# GSM_GPS.net
KiCad netlist of a schematic drawn in Altium Designer
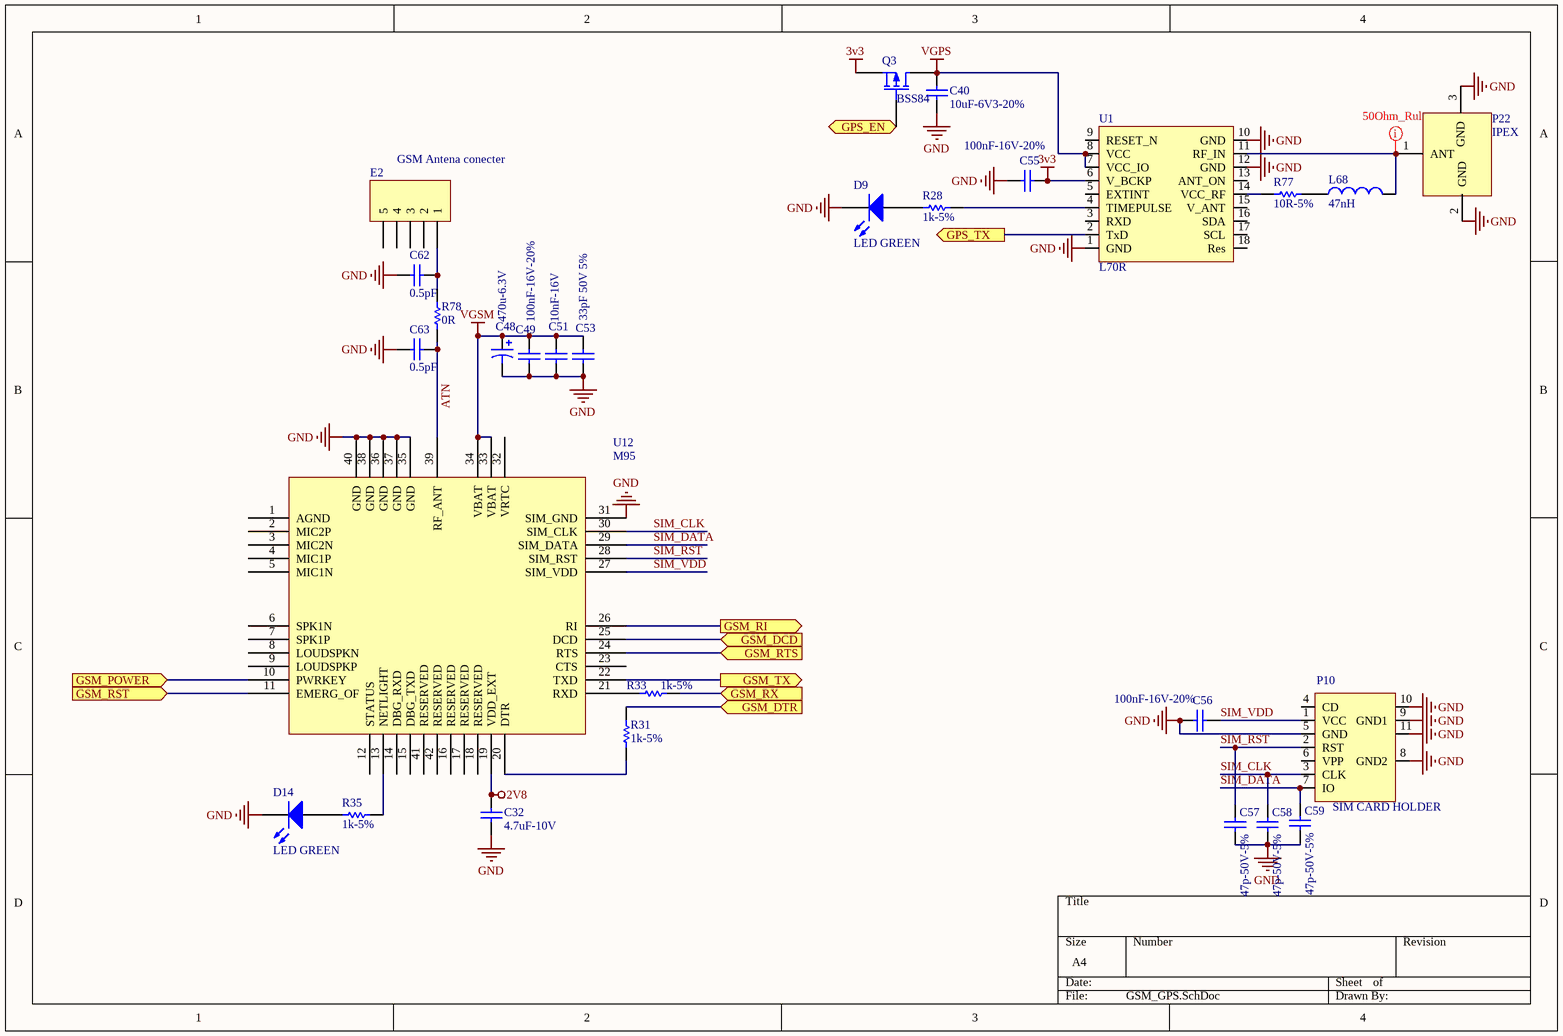
[diagram p0: GSM_GPS.SchDoc]

(export (version "E")
  (design (tool "Eeschema 10.0.6"))
  (components
    (comp (ref "C32")
      (value "4.7uF-10V")
      (footprint "C0603")
      (description "Non-Polarized Capacitor")
      (fields (field (name "DIGI-KEY PART NUMBER") "311-1371-1-ND") (field (name "MANUFACTURER") "Yageo"))
      (libsource (lib "Capacitor") (part "4.7uF-10V-C0805"))
    )
    (comp (ref "C40")
      (value "10uF-6V3-20%")
      (footprint "C0603")
      (description "CAP CER 10UF 6.3V 20% X5R 0603")
      (fields
        (field (name "MANUFACTURER") "Murata Electronics North America")
        (field (name "DIGI-KEY PART NUMBER") "490-3896-1-ND")
        (field (name "PUBLISHER") "Altium Limited")
      )
      (libsource (lib "Miscellaneous Devices") (part "Cap"))
    )
    (comp (ref "C48")
      (value "470u-6.3V")
      (footprint "C1812")
      (description "CAP CER 100UF 10V 20% X5R 1812")
      (fields
        (field (name "DIGI-KEY PART NUMBER") "445-7743-2-ND")
        (field (name "MANUFACTURER PART NUMBER") "C4532X5R1A107M")
        (field (name "PUBLISHER") "Altium Limited")
      )
      (libsource (lib "Miscellaneous Devices") (part "Cap Pol3"))
    )
    (comp (ref "C49")
      (value "100nF-16V-20%")
      (footprint "C0402")
      (description "CAP CER 0.1UF 16V Y5V 0402")
      (fields
        (field (name "MANUFACTURER") "Yageo")
        (field (name "DIGI-KEY PART NUMBER") "311-1047-1-ND")
        (field (name "PUBLISHER") "Altium Limited")
      )
      (libsource (lib "Miscellaneous Devices") (part "Cap"))
    )
    (comp (ref "C51")
      (value "10nF-16V")
      (footprint "C0402")
      (description "CAP CER 10000PF 16V 10% X7R 0402")
      (fields (field (name "DIGI-KEY PART NUMBER") "311-1042-2-ND") (field (name "MANUFACTURER") "Yageo"))
      (libsource (lib "Capacitor_0402") (part "10nF-16V-C0402-10%"))
    )
    (comp (ref "C53")
      (value "33pF 50V 5%")
      (footprint "C0402")
      (description "CAP CER 68PF 50V 5% NPO 0402")
      (fields (field (name "MANUFACTURER") "Yageo") (field (name "DIGI-KEY PART NUMBER") "311-1340-2-ND"))
      (libsource (lib "Miscellaneous Devices") (part "Cap"))
    )
    (comp (ref "C55")
      (value "100nF-16V-20%")
      (footprint "C0402")
      (description "CAP CER 0.1UF 16V Y5V 0402")
      (fields
        (field (name "MANUFACTURER") "Yageo")
        (field (name "DIGI-KEY PART NUMBER") "311-1047-1-ND")
        (field (name "PUBLISHER") "Altium Limited")
      )
      (libsource (lib "Miscellaneous Devices") (part "Cap"))
    )
    (comp (ref "C56")
      (value "100nF-16V-20%")
      (footprint "C0402")
      (description "CAP CER 0.1UF 16V Y5V 0402")
      (fields
        (field (name "MANUFACTURER") "Yageo")
        (field (name "DIGI-KEY PART NUMBER") "311-1047-1-ND")
        (field (name "PUBLISHER") "Altium Limited")
      )
      (libsource (lib "Miscellaneous Devices") (part "Cap"))
    )
    (comp (ref "C57")
      (value "47p-50V-5%")
      (footprint "C0402")
      (description "CAP CER 47PF 50V 5% NPO 0402")
      (fields
        (field (name "MANUFACTURER") "Yageo")
        (field (name "DIGI-KEY PART NUMBER") "311-1021-1-ND")
        (field (name "PUBLISHER") "Altium Limited")
      )
      (libsource (lib "Miscellaneous Devices") (part "Cap"))
    )
    (comp (ref "C58")
      (value "47p-50V-5%")
      (footprint "C0402")
      (description "CAP CER 47PF 50V 5% NPO 0402")
      (fields
        (field (name "MANUFACTURER") "Yageo")
        (field (name "DIGI-KEY PART NUMBER") "311-1021-1-ND")
        (field (name "PUBLISHER") "Altium Limited")
      )
      (libsource (lib "Miscellaneous Devices") (part "Cap"))
    )
    (comp (ref "C59")
      (value "47p-50V-5%")
      (footprint "C0402")
      (description "CAP CER 47PF 50V 5% NPO 0402")
      (fields
        (field (name "MANUFACTURER") "Yageo")
        (field (name "DIGI-KEY PART NUMBER") "311-1021-1-ND")
        (field (name "PUBLISHER") "Altium Limited")
      )
      (libsource (lib "Miscellaneous Devices") (part "Cap"))
    )
    (comp (ref "C62")
      (value "0.5pF")
      (footprint "C0402")
      (description "Non-Polarized Capacitor")
      (fields (field (name "DIGI-KEY PART NUMBER") "311-1094-1-ND") (field (name "MANUFACTURER") "Yageo"))
      (libsource (lib "Capacitor") (part "0.5pF-50V-C0805"))
    )
    (comp (ref "C63")
      (value "0.5pF")
      (footprint "C0402")
      (description "Non-Polarized Capacitor")
      (fields (field (name "DIGI-KEY PART NUMBER") "311-1094-1-ND") (field (name "MANUFACTURER") "Yageo"))
      (libsource (lib "Capacitor") (part "0.5pF-50V-C0805"))
    )
    (comp (ref "D9")
      (value "LED GREEN")
      (footprint "LED0603-G")
      (description "LED GREEN CLEAR THIN 0603 SMD")
      (fields
        (field (name "DIGI-KEY PART NUMBER") "160-1446-2-ND")
        (field (name "MANUFACTURER") "Lite-On Inc")
        (field (name "PUBLISHER") "Altium Limited")
      )
      (libsource (lib "Miscellaneous Devices") (part "LED2"))
    )
    (comp (ref "D14")
      (value "LED GREEN")
      (footprint "LED0603-G")
      (description "LED GREEN CLEAR THIN 0603 SMD")
      (fields
        (field (name "DIGI-KEY PART NUMBER") "160-1446-2-ND")
        (field (name "MANUFACTURER") "Lite-On Inc")
        (field (name "PUBLISHER") "Altium Limited")
      )
      (libsource (lib "Miscellaneous Devices") (part "LED2"))
    )
    (comp (ref "E2")
      (value "GSM Antena conecter")
      (footprint "A10343-GSM850/900/1800/1900/WCDMA")
      (description "Header, 5-Pin")
      (fields (field (name "PUBLISHER") "Altium Limited"))
      (libsource (lib "Miscellaneous Connectors") (part "Header 5"))
    )
    (comp (ref "L68")
      (value "47nH")
      (footprint "C0603")
      (description "Inductor")
      (fields (field (name "PUBLISHER") "Altium Limited"))
      (libsource (lib "Miscellaneous Devices") (part "Inductor"))
    )
    (comp (ref "P10")
      (value "SIM CARD HOLDER")
      (footprint "SIM MF01-412-063X")
      (description "SIM _CONNECTOR_410108105011-2LF")
      (fields (field (name "MANUFACTURER") "Tyrone"))
      (libsource (lib "Schlib1") (part "SIM CARD"))
    )
    (comp (ref "P22") (value "IPEX") (footprint "IPEX") (libsource (lib "Schlib1") (part "IPEX")))
    (comp (ref "Q3")
      (value "BSS84")
      (footprint "SOT23-3")
      (description "MOSFET P-CH 50V 130MA SOT23-3")
      (fields
        (field (name "DIGI-KEY PART NUMBER") "BSS84-FDITR-ND")
        (field (name "MANUFACTURER") "Diodes Inc")
        (field (name "PUBLISHER") "Altium Limited")
      )
      (libsource (lib "Miscellaneous Devices") (part "MOSFET-P"))
    )
    (comp (ref "R28")
      (value "1k-5%")
      (footprint "R0402")
      (description "RES 1.0K OHM 1/16W 5% 0402 SMD")
      (fields
        (field (name "DIGI-KEY PART NUMBER") "311-1.0KJRCT-ND")
        (field (name "MANUFACTURER") "Yageo")
        (field (name "PUBLISHER") "Altium Limited")
      )
      (libsource (lib "Miscellaneous Devices") (part "Res1"))
    )
    (comp (ref "R31")
      (value "1k-5%")
      (footprint "R0402")
      (description "RES 1.0K OHM 1/16W 5% 0402 SMD")
      (fields
        (field (name "DIGI-KEY PART NUMBER") "311-1.0KJRCT-ND")
        (field (name "MANUFACTURER") "Yageo")
        (field (name "PUBLISHER") "Altium Limited")
      )
      (libsource (lib "Miscellaneous Devices") (part "Res1"))
    )
    (comp (ref "R33")
      (value "1k-5%")
      (footprint "R0402")
      (description "RES 1.0K OHM 1/16W 5% 0402 SMD")
      (fields
        (field (name "DIGI-KEY PART NUMBER") "311-1.0KJRCT-ND")
        (field (name "MANUFACTURER") "Yageo")
        (field (name "PUBLISHER") "Altium Limited")
      )
      (libsource (lib "Miscellaneous Devices") (part "Res1"))
    )
    (comp (ref "R35")
      (value "1k-5%")
      (footprint "R0402")
      (description "RES 1.0K OHM 1/16W 5% 0402 SMD")
      (fields
        (field (name "DIGI-KEY PART NUMBER") "311-1.0KJRCT-ND")
        (field (name "MANUFACTURER") "Yageo")
        (field (name "PUBLISHER") "Altium Limited")
      )
      (libsource (lib "Miscellaneous Devices") (part "Res1"))
    )
    (comp (ref "R77")
      (value "10R-5%")
      (footprint "R0402")
      (description "RES 10 OHM 1/16W 5% 0402 SMD")
      (fields (field (name "DIGI-KEY PART NUMBER") "311-10JRTR-ND") (field (name "MANUFACTURER") "Yageo"))
      (libsource (lib "Resistor_0402") (part "10R-5%-R0402"))
    )
    (comp (ref "R78") (value "0R") (footprint "R0402") (libsource (lib "All_Resistor") (part "0R-0805")))
    (comp (ref "U1") (value "L70R") (footprint "MAX7") (libsource (lib "U-Blox") (part "MAX-7")))
    (comp (ref "U12") (value "M95") (footprint "M95") (libsource (lib "PJ2000V2") (part "M95")))
  )
  (nets
    (net (code "1") (name "/ATN") (class "Default")
      (node (ref "C63") (pin "2") (pinfunction "2_2") (pintype "passive"))
      (node (ref "R78") (pin "1") (pinfunction "1_1") (pintype "passive"))
      (node (ref "U12") (pin "39") (pinfunction "RF_ANT_39") (pintype "passive"))
    )
    (net (code "2") (name "/GPS_EN") (class "Default")
      (node (ref "Q3") (pin "1") (pinfunction "G_1") (pintype "passive"))
    )
    (net (code "3") (name "/GPS_TX") (class "Default")
      (node (ref "U1") (pin "2") (pinfunction "TxD_2") (pintype "passive"))
    )
    (net (code "4") (name "/GSM_DCD") (class "Default")
      (node (ref "U12") (pin "25") (pinfunction "DCD_25") (pintype "passive"))
    )
    (net (code "5") (name "/GSM_DTR") (class "Default")
      (node (ref "R31") (pin "1") (pinfunction "1_1") (pintype "passive"))
    )
    (net (code "6") (name "/GSM_POWER") (class "Default")
      (node (ref "U12") (pin "10") (pinfunction "PWRKEY_10") (pintype "passive"))
    )
    (net (code "7") (name "/GSM_RI") (class "Default")
      (node (ref "U12") (pin "26") (pinfunction "RI_26") (pintype "passive"))
    )
    (net (code "8") (name "/GSM_RST") (class "Default")
      (node (ref "U12") (pin "11") (pinfunction "EMERG_OF_11") (pintype "passive"))
    )
    (net (code "9") (name "/GSM_RTS") (class "Default")
      (node (ref "U12") (pin "24") (pinfunction "RTS_24") (pintype "passive"))
    )
    (net (code "10") (name "/GSM_RX") (class "Default")
      (node (ref "R33") (pin "1") (pinfunction "1_1") (pintype "passive"))
    )
    (net (code "11") (name "/GSM_TX") (class "Default")
      (node (ref "U12") (pin "22") (pinfunction "TXD_22") (pintype "passive"))
    )
    (net (code "12") (name "/SIM_CLK") (class "Default")
      (node (ref "C58") (pin "2") (pinfunction "2_2") (pintype "passive"))
      (node (ref "P10") (pin "3") (pinfunction "CLK_3") (pintype "passive"))
      (node (ref "U12") (pin "30") (pinfunction "SIM_CLK_30") (pintype "passive"))
    )
    (net (code "13") (name "/SIM_DATA") (class "Default")
      (node (ref "C59") (pin "2") (pinfunction "2_2") (pintype "passive"))
      (node (ref "P10") (pin "7") (pinfunction "IO_7") (pintype "passive"))
      (node (ref "U12") (pin "29") (pinfunction "SIM_DATA_29") (pintype "passive"))
    )
    (net (code "14") (name "/SIM_RST") (class "Default")
      (node (ref "C57") (pin "2") (pinfunction "2_2") (pintype "passive"))
      (node (ref "P10") (pin "2") (pinfunction "RST_2") (pintype "passive"))
      (node (ref "U12") (pin "28") (pinfunction "SIM_RST_28") (pintype "passive"))
    )
    (net (code "15") (name "/SIM_VDD") (class "Default")
      (node (ref "C56") (pin "1") (pinfunction "1_1") (pintype "passive"))
      (node (ref "P10") (pin "1") (pinfunction "VCC_1") (pintype "passive"))
      (node (ref "U12") (pin "27") (pinfunction "SIM_VDD_27") (pintype "passive"))
    )
    (net (code "16") (name "2V8") (class "Default")
      (node (ref "C32") (pin "2") (pinfunction "2_2") (pintype "passive"))
      (node (ref "U12") (pin "19") (pinfunction "VDD_EXT_19") (pintype "passive"))
    )
    (net (code "17") (name "3v3") (class "Default")
      (node (ref "C55") (pin "1") (pinfunction "1_1") (pintype "passive"))
      (node (ref "Q3") (pin "2") (pinfunction "S_2") (pintype "passive"))
      (node (ref "U1") (pin "6") (pinfunction "V_BCKP_6") (pintype "passive"))
    )
    (net (code "18") (name "GND") (class "Default")
      (node (ref "C32") (pin "1") (pinfunction "1_1") (pintype "passive"))
      (node (ref "C40") (pin "1") (pinfunction "1_1") (pintype "passive"))
      (node (ref "C48") (pin "2") (pinfunction "2_2") (pintype "passive"))
      (node (ref "C49") (pin "2") (pinfunction "2_2") (pintype "passive"))
      (node (ref "C51") (pin "1") (pinfunction "1_1") (pintype "passive"))
      (node (ref "C53") (pin "2") (pinfunction "2_2") (pintype "passive"))
      (node (ref "C55") (pin "2") (pinfunction "2_2") (pintype "passive"))
      (node (ref "C56") (pin "2") (pinfunction "2_2") (pintype "passive"))
      (node (ref "C57") (pin "1") (pinfunction "1_1") (pintype "passive"))
      (node (ref "C58") (pin "1") (pinfunction "1_1") (pintype "passive"))
      (node (ref "C59") (pin "1") (pinfunction "1_1") (pintype "passive"))
      (node (ref "C62") (pin "1") (pinfunction "1_1") (pintype "passive"))
      (node (ref "C63") (pin "1") (pinfunction "1_1") (pintype "passive"))
      (node (ref "D14") (pin "2") (pinfunction "K_2") (pintype "passive"))
      (node (ref "D9") (pin "2") (pinfunction "K_2") (pintype "passive"))
      (node (ref "P10") (pin "10") (pinfunction "GND3_10") (pintype "passive"))
      (node (ref "P10") (pin "11") (pinfunction "GND4_11") (pintype "passive"))
      (node (ref "P10") (pin "5") (pinfunction "GND_5") (pintype "passive"))
      (node (ref "P10") (pin "8") (pinfunction "GND2_8") (pintype "passive"))
      (node (ref "P10") (pin "9") (pinfunction "GND1_9") (pintype "passive"))
      (node (ref "P22") (pin "2") (pinfunction "GND_2") (pintype "passive"))
      (node (ref "P22") (pin "3") (pinfunction "GND_3") (pintype "passive"))
      (node (ref "U1") (pin "1") (pinfunction "GND_1") (pintype "passive"))
      (node (ref "U1") (pin "10") (pinfunction "GND_10") (pintype "passive"))
      (node (ref "U1") (pin "12") (pinfunction "GND_12") (pintype "passive"))
      (node (ref "U12") (pin "31") (pinfunction "SIM_GND_31") (pintype "passive"))
      (node (ref "U12") (pin "35") (pinfunction "GND_35") (pintype "passive"))
      (node (ref "U12") (pin "36") (pinfunction "GND_36") (pintype "passive"))
      (node (ref "U12") (pin "37") (pinfunction "GND_37") (pintype "passive"))
      (node (ref "U12") (pin "38") (pinfunction "GND_38") (pintype "passive"))
      (node (ref "U12") (pin "40") (pinfunction "GND_40") (pintype "passive"))
    )
    (net (code "19") (name "Net-(C62-Pad2)") (class "Default")
      (node (ref "C62") (pin "2") (pinfunction "2_2") (pintype "passive"))
      (node (ref "E2") (pin "1") (pinfunction "1_1") (pintype "passive"))
      (node (ref "R78") (pin "2") (pinfunction "2_2") (pintype "passive"))
    )
    (net (code "20") (name "Net-(D9-A)") (class "Default")
      (node (ref "D9") (pin "1") (pinfunction "A_1") (pintype "passive"))
      (node (ref "R28") (pin "2") (pinfunction "2_2") (pintype "passive"))
    )
    (net (code "21") (name "Net-(D14-A)") (class "Default")
      (node (ref "D14") (pin "1") (pinfunction "A_1") (pintype "passive"))
      (node (ref "R35") (pin "1") (pinfunction "1_1") (pintype "passive"))
    )
    (net (code "22") (name "Net-(L68-Pad1)") (class "Default")
      (node (ref "L68") (pin "1") (pinfunction "1_1") (pintype "passive"))
      (node (ref "R77") (pin "1") (pinfunction "1_1") (pintype "passive"))
    )
    (net (code "23") (name "Net-(P22-ANT)") (class "Default")
      (node (ref "L68") (pin "2") (pinfunction "2_2") (pintype "passive"))
      (node (ref "P22") (pin "1") (pinfunction "ANT_1") (pintype "passive"))
      (node (ref "U1") (pin "11") (pinfunction "RF_IN_11") (pintype "passive"))
    )
    (net (code "24") (name "Net-(U1-TIMEPULSE)") (class "Default")
      (node (ref "R28") (pin "1") (pinfunction "1_1") (pintype "passive"))
      (node (ref "U1") (pin "4") (pinfunction "TIMEPULSE_4") (pintype "passive"))
    )
    (net (code "25") (name "Net-(U1-VCC_RF)") (class "Default")
      (node (ref "R77") (pin "2") (pinfunction "2_2") (pintype "passive"))
      (node (ref "U1") (pin "14") (pinfunction "VCC_RF_14") (pintype "passive"))
    )
    (net (code "26") (name "Net-(U12-DTR)") (class "Default")
      (node (ref "R31") (pin "2") (pinfunction "2_2") (pintype "passive"))
      (node (ref "U12") (pin "20") (pinfunction "DTR_20") (pintype "passive"))
    )
    (net (code "27") (name "Net-(U12-NETLIGHT)") (class "Default")
      (node (ref "R35") (pin "2") (pinfunction "2_2") (pintype "passive"))
      (node (ref "U12") (pin "13") (pinfunction "NETLIGHT_13") (pintype "passive"))
    )
    (net (code "28") (name "Net-(U12-RXD)") (class "Default")
      (node (ref "R33") (pin "2") (pinfunction "2_2") (pintype "passive"))
      (node (ref "U12") (pin "21") (pinfunction "RXD_21") (pintype "passive"))
    )
    (net (code "29") (name "VGPS") (class "Default")
      (node (ref "C40") (pin "2") (pinfunction "2_2") (pintype "passive"))
      (node (ref "Q3") (pin "3") (pinfunction "D_3") (pintype "passive"))
      (node (ref "U1") (pin "7") (pinfunction "VCC_IO_7") (pintype "passive"))
      (node (ref "U1") (pin "8") (pinfunction "VCC_8") (pintype "passive"))
    )
    (net (code "30") (name "VGSM") (class "Default")
      (node (ref "C48") (pin "1") (pinfunction "1_1") (pintype "passive"))
      (node (ref "C49") (pin "1") (pinfunction "1_1") (pintype "passive"))
      (node (ref "C51") (pin "2") (pinfunction "2_2") (pintype "passive"))
      (node (ref "C53") (pin "1") (pinfunction "1_1") (pintype "passive"))
      (node (ref "U12") (pin "33") (pinfunction "VBAT_33") (pintype "passive"))
      (node (ref "U12") (pin "34") (pinfunction "VBAT_34") (pintype "passive"))
    )
    (net (code "31") (name "unconnected-(E2-Pad2)") (class "Default")
      (node (ref "E2") (pin "2") (pinfunction "2_2") (pintype "passive"))
    )
    (net (code "32") (name "unconnected-(E2-Pad3)") (class "Default")
      (node (ref "E2") (pin "3") (pinfunction "3_3") (pintype "passive"))
    )
    (net (code "33") (name "unconnected-(E2-Pad4)") (class "Default")
      (node (ref "E2") (pin "4") (pinfunction "4_4") (pintype "passive"))
    )
    (net (code "34") (name "unconnected-(E2-Pad5)") (class "Default")
      (node (ref "E2") (pin "5") (pinfunction "5_5") (pintype "passive"))
    )
    (net (code "35") (name "unconnected-(P10-CD-Pad4)") (class "Default")
      (node (ref "P10") (pin "4") (pinfunction "CD_4") (pintype "passive"))
    )
    (net (code "36") (name "unconnected-(P10-VPP-Pad6)") (class "Default")
      (node (ref "P10") (pin "6") (pinfunction "VPP_6") (pintype "passive"))
    )
    (net (code "37") (name "unconnected-(U1-ANT_ON-Pad13)") (class "Default")
      (node (ref "U1") (pin "13") (pinfunction "ANT_ON_13") (pintype "passive"))
    )
    (net (code "38") (name "unconnected-(U1-EXTINT-Pad5)") (class "Default")
      (node (ref "U1") (pin "5") (pinfunction "EXTINT_5") (pintype "passive"))
    )
    (net (code "39") (name "unconnected-(U1-RESET_N-Pad9)") (class "Default")
      (node (ref "U1") (pin "9") (pinfunction "RESET_N_9") (pintype "passive"))
    )
    (net (code "40") (name "unconnected-(U1-RXD-Pad3)") (class "Default")
      (node (ref "U1") (pin "3") (pinfunction "RXD_3") (pintype "passive"))
    )
    (net (code "41") (name "unconnected-(U1-Res-Pad18)") (class "Default")
      (node (ref "U1") (pin "18") (pinfunction "Res_18") (pintype "passive"))
    )
    (net (code "42") (name "unconnected-(U1-SCL-Pad17)") (class "Default")
      (node (ref "U1") (pin "17") (pinfunction "SCL_17") (pintype "passive"))
    )
    (net (code "43") (name "unconnected-(U1-SDA-Pad16)") (class "Default")
      (node (ref "U1") (pin "16") (pinfunction "SDA_16") (pintype "passive"))
    )
    (net (code "44") (name "unconnected-(U1-V_ANT-Pad15)") (class "Default")
      (node (ref "U1") (pin "15") (pinfunction "V_ANT_15") (pintype "passive"))
    )
    (net (code "45") (name "unconnected-(U12-AGND-Pad1)") (class "Default")
      (node (ref "U12") (pin "1") (pinfunction "AGND_1") (pintype "passive"))
    )
    (net (code "46") (name "unconnected-(U12-CTS-Pad23)") (class "Default")
      (node (ref "U12") (pin "23") (pinfunction "CTS_23") (pintype "passive"))
    )
    (net (code "47") (name "unconnected-(U12-DBG_RXD-Pad14)") (class "Default")
      (node (ref "U12") (pin "14") (pinfunction "DBG_RXD_14") (pintype "passive"))
    )
    (net (code "48") (name "unconnected-(U12-DBG_TXD-Pad15)") (class "Default")
      (node (ref "U12") (pin "15") (pinfunction "DBG_TXD_15") (pintype "passive"))
    )
    (net (code "49") (name "unconnected-(U12-LOUDSPKN-Pad8)") (class "Default")
      (node (ref "U12") (pin "8") (pinfunction "LOUDSPKN_8") (pintype "passive"))
    )
    (net (code "50") (name "unconnected-(U12-LOUDSPKP-Pad9)") (class "Default")
      (node (ref "U12") (pin "9") (pinfunction "LOUDSPKP_9") (pintype "passive"))
    )
    (net (code "51") (name "unconnected-(U12-MIC1N-Pad5)") (class "Default")
      (node (ref "U12") (pin "5") (pinfunction "MIC1N_5") (pintype "passive"))
    )
    (net (code "52") (name "unconnected-(U12-MIC1P-Pad4)") (class "Default")
      (node (ref "U12") (pin "4") (pinfunction "MIC1P_4") (pintype "passive"))
    )
    (net (code "53") (name "unconnected-(U12-MIC2N-Pad3)") (class "Default")
      (node (ref "U12") (pin "3") (pinfunction "MIC2N_3") (pintype "passive"))
    )
    (net (code "54") (name "unconnected-(U12-MIC2P-Pad2)") (class "Default")
      (node (ref "U12") (pin "2") (pinfunction "MIC2P_2") (pintype "passive"))
    )
    (net (code "55") (name "unconnected-(U12-RESERVED-Pad16)") (class "Default")
      (node (ref "U12") (pin "16") (pinfunction "RESERVED_16") (pintype "passive"))
    )
    (net (code "56") (name "unconnected-(U12-RESERVED-Pad17)") (class "Default")
      (node (ref "U12") (pin "17") (pinfunction "RESERVED_17") (pintype "passive"))
    )
    (net (code "57") (name "unconnected-(U12-RESERVED-Pad18)") (class "Default")
      (node (ref "U12") (pin "18") (pinfunction "RESERVED_18") (pintype "passive"))
    )
    (net (code "58") (name "unconnected-(U12-RESERVED-Pad41)") (class "Default")
      (node (ref "U12") (pin "41") (pinfunction "RESERVED_41") (pintype "passive"))
    )
    (net (code "59") (name "unconnected-(U12-RESERVED-Pad42)") (class "Default")
      (node (ref "U12") (pin "42") (pinfunction "RESERVED_42") (pintype "passive"))
    )
    (net (code "60") (name "unconnected-(U12-SPK1N-Pad6)") (class "Default")
      (node (ref "U12") (pin "6") (pinfunction "SPK1N_6") (pintype "passive"))
    )
    (net (code "61") (name "unconnected-(U12-SPK1P-Pad7)") (class "Default")
      (node (ref "U12") (pin "7") (pinfunction "SPK1P_7") (pintype "passive"))
    )
    (net (code "62") (name "unconnected-(U12-STATUS-Pad12)") (class "Default")
      (node (ref "U12") (pin "12") (pinfunction "STATUS_12") (pintype "passive"))
    )
    (net (code "63") (name "unconnected-(U12-VRTC-Pad32)") (class "Default")
      (node (ref "U12") (pin "32") (pinfunction "VRTC_32") (pintype "passive"))
    )
  )
)
